# MotionDetectorProgJIG.net
KiCad netlist of a schematic drawn in Altium Designer
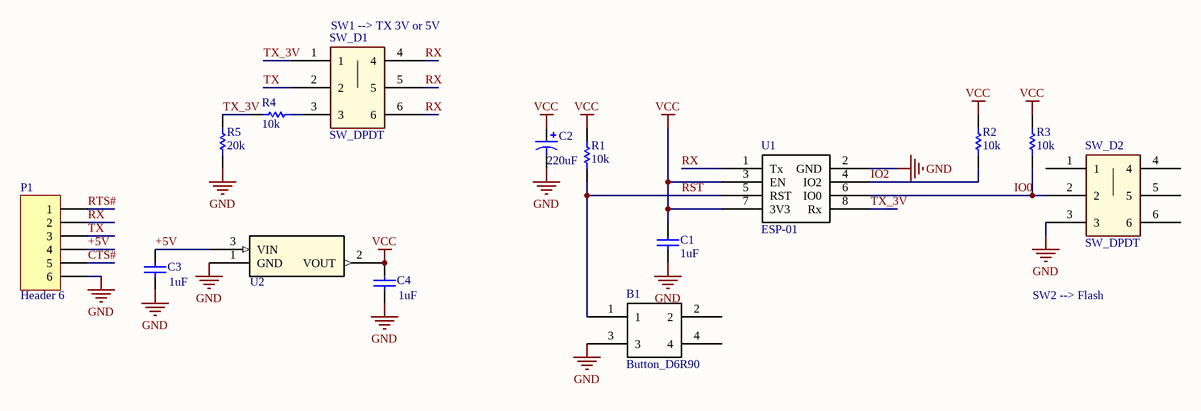
[diagram p0: MotionDetectorProgJIG.SchDoc]

(export (version "E")
  (design (tool "Eeschema 10.0.6"))
  (components
    (comp (ref "B1")
      (value "Button_D6R90")
      (footprint "Button_D6R90")
      (libsource (lib "MotionDetectorSchematicLib") (part "Button_D6R90"))
    )
    (comp (ref "C1")
      (value "1uF")
      (footprint "CAP_0804")
      (description "Capacitor")
      (fields (field (name "Comment") "Cap") (field (name "PUBLISHER") "Altium Limited"))
      (libsource (lib "Miscellaneous Devices") (part "Cap"))
    )
    (comp (ref "C2")
      (value "220uF")
      (footprint "U2-K")
      (description "Polarized Capacitor (Radial)")
      (fields (field (name "Comment") "Cap Pol1") (field (name "PUBLISHER") "Altium Limited"))
      (libsource (lib "Miscellaneous Devices") (part "Cap Pol1"))
    )
    (comp (ref "C3")
      (value "1uF")
      (footprint "CAP_0804")
      (description "Capacitor")
      (fields (field (name "Comment") "Cap") (field (name "PUBLISHER") "Altium Limited"))
      (libsource (lib "Miscellaneous Devices") (part "Cap"))
    )
    (comp (ref "C4")
      (value "1uF")
      (footprint "CAP_0804")
      (description "Capacitor")
      (fields (field (name "Comment") "Cap") (field (name "PUBLISHER") "Altium Limited"))
      (libsource (lib "Miscellaneous Devices") (part "Cap"))
    )
    (comp (ref "P1")
      (value "Header 6")
      (footprint "HDR1X6")
      (description "Header, 6-Pin")
      (fields (field (name "PUBLISHER") "Altium Limited"))
      (libsource (lib "Miscellaneous Connectors") (part "Header 6"))
    )
    (comp (ref "R1")
      (value "10k")
      (footprint "RES_0804_panasonic")
      (description "Resistor")
      (fields (field (name "Comment") "Res1") (field (name "PUBLISHER") "Altium Limited"))
      (libsource (lib "Miscellaneous Devices") (part "Res1"))
    )
    (comp (ref "R2")
      (value "10k")
      (footprint "RES_0804_panasonic")
      (description "Resistor")
      (fields (field (name "Comment") "Res1") (field (name "PUBLISHER") "Altium Limited"))
      (libsource (lib "Miscellaneous Devices") (part "Res1"))
    )
    (comp (ref "R3")
      (value "10k")
      (footprint "RES_0804_panasonic")
      (description "Resistor")
      (fields (field (name "Comment") "Res1") (field (name "PUBLISHER") "Altium Limited"))
      (libsource (lib "Miscellaneous Devices") (part "Res1"))
    )
    (comp (ref "R4")
      (value "10k")
      (footprint "RES_0804_panasonic")
      (description "Resistor")
      (fields (field (name "Comment") "Res1") (field (name "PUBLISHER") "Altium Limited"))
      (libsource (lib "Miscellaneous Devices") (part "Res1"))
    )
    (comp (ref "R5")
      (value "20k")
      (footprint "RES_0804_panasonic")
      (description "Resistor")
      (fields (field (name "Comment") "Res1") (field (name "PUBLISHER") "Altium Limited"))
      (libsource (lib "Miscellaneous Devices") (part "Res1"))
    )
    (comp (ref "SW_D1")
      (value "SW_DPDT")
      (footprint "SW_DPDT")
      (libsource (lib "MotionDetectorSchematicLib") (part "SW_DPDT"))
    )
    (comp (ref "SW_D2")
      (value "SW_DPDT")
      (footprint "SW_DPDT")
      (libsource (lib "MotionDetectorSchematicLib") (part "SW_DPDT"))
    )
    (comp (ref "U1")
      (value "ESP-01")
      (footprint "ESP-01")
      (libsource (lib "MotionDetectorSchematicLib") (part "ESP-01"))
    )
    (comp (ref "U2")
      (value "Voltage Reg")
      (footprint "SOT-23")
      (fields (field (name "MANUFACTURER_PART_NUMBER") "AP2120N-3.3TRG1"))
      (libsource (lib "MotionDetectorSchematicLib") (part "AP2120N-3.3TRG1"))
    )
  )
  (nets
    (net (code "1") (name "/+5V") (class "Default")
      (node (ref "C3") (pin "2") (pinfunction "2_2") (pintype "passive"))
      (node (ref "P1") (pin "4") (pinfunction "4_4") (pintype "passive"))
      (node (ref "U2") (pin "3") (pinfunction "VIN_3") (pintype "input"))
    )
    (net (code "2") (name "/CTS#") (class "Default")
      (node (ref "P1") (pin "5") (pinfunction "5_5") (pintype "passive"))
    )
    (net (code "3") (name "/IO0") (class "Default")
      (node (ref "R3") (pin "1") (pinfunction "1_1") (pintype "passive"))
      (node (ref "SW_D2") (pin "2") (pinfunction "2_2") (pintype "passive"))
      (node (ref "U1") (pin "6") (pinfunction "IO0_6") (pintype "passive"))
    )
    (net (code "4") (name "/IO2") (class "Default")
      (node (ref "R2") (pin "1") (pinfunction "1_1") (pintype "passive"))
      (node (ref "U1") (pin "4") (pinfunction "IO2_4") (pintype "passive"))
    )
    (net (code "5") (name "/RST") (class "Default")
      (node (ref "B1") (pin "1") (pinfunction "1_1") (pintype "passive"))
      (node (ref "R1") (pin "1") (pinfunction "1_1") (pintype "passive"))
      (node (ref "U1") (pin "5") (pinfunction "RST_5") (pintype "passive"))
    )
    (net (code "6") (name "/RTS#") (class "Default")
      (node (ref "P1") (pin "1") (pinfunction "1_1") (pintype "passive"))
    )
    (net (code "7") (name "/RX") (class "Default")
      (node (ref "P1") (pin "2") (pinfunction "2_2") (pintype "passive"))
      (node (ref "SW_D1") (pin "4") (pinfunction "4_4") (pintype "passive"))
      (node (ref "SW_D1") (pin "5") (pinfunction "5_5") (pintype "passive"))
      (node (ref "SW_D1") (pin "6") (pinfunction "6_6") (pintype "passive"))
      (node (ref "U1") (pin "1") (pinfunction "Tx_1") (pintype "passive"))
    )
    (net (code "8") (name "/TX") (class "Default")
      (node (ref "P1") (pin "3") (pinfunction "3_3") (pintype "passive"))
      (node (ref "SW_D1") (pin "2") (pinfunction "2_2") (pintype "passive"))
    )
    (net (code "9") (name "/TX_3V") (class "Default")
      (node (ref "R4") (pin "2") (pinfunction "2_2") (pintype "passive"))
      (node (ref "R5") (pin "1") (pinfunction "1_1") (pintype "passive"))
      (node (ref "SW_D1") (pin "1") (pinfunction "1_1") (pintype "passive"))
      (node (ref "U1") (pin "8") (pinfunction "Rx_8") (pintype "passive"))
    )
    (net (code "10") (name "GND") (class "Default")
      (node (ref "B1") (pin "3") (pinfunction "3_3") (pintype "passive"))
      (node (ref "C1") (pin "2") (pinfunction "2_2") (pintype "passive"))
      (node (ref "C2") (pin "2") (pinfunction "2_2") (pintype "passive"))
      (node (ref "C3") (pin "1") (pinfunction "1_1") (pintype "passive"))
      (node (ref "C4") (pin "1") (pinfunction "1_1") (pintype "passive"))
      (node (ref "P1") (pin "6") (pinfunction "6_6") (pintype "passive"))
      (node (ref "R5") (pin "2") (pinfunction "2_2") (pintype "passive"))
      (node (ref "SW_D2") (pin "3") (pinfunction "3_3") (pintype "passive"))
      (node (ref "U1") (pin "2") (pinfunction "GND_2") (pintype "passive"))
      (node (ref "U2") (pin "1") (pinfunction "GND_1") (pintype "power_in"))
    )
    (net (code "11") (name "Net-(R4-Pad1)") (class "Default")
      (node (ref "R4") (pin "1") (pinfunction "1_1") (pintype "passive"))
      (node (ref "SW_D1") (pin "3") (pinfunction "3_3") (pintype "passive"))
    )
    (net (code "12") (name "VCC") (class "Default")
      (node (ref "C1") (pin "1") (pinfunction "1_1") (pintype "passive"))
      (node (ref "C2") (pin "1") (pinfunction "1_1") (pintype "passive"))
      (node (ref "C4") (pin "2") (pinfunction "2_2") (pintype "passive"))
      (node (ref "R1") (pin "2") (pinfunction "2_2") (pintype "passive"))
      (node (ref "R2") (pin "2") (pinfunction "2_2") (pintype "passive"))
      (node (ref "R3") (pin "2") (pinfunction "2_2") (pintype "passive"))
      (node (ref "U1") (pin "3") (pinfunction "EN_3") (pintype "passive"))
      (node (ref "U1") (pin "7") (pinfunction "3V3_7") (pintype "passive"))
      (node (ref "U2") (pin "2") (pinfunction "VOUT_2") (pintype "output"))
    )
    (net (code "13") (name "unconnected-(B1-Pad2)") (class "Default")
      (node (ref "B1") (pin "2") (pinfunction "2_2") (pintype "passive"))
    )
    (net (code "14") (name "unconnected-(B1-Pad4)") (class "Default")
      (node (ref "B1") (pin "4") (pinfunction "4_4") (pintype "passive"))
    )
    (net (code "15") (name "unconnected-(SW_D2-Pad1)") (class "Default")
      (node (ref "SW_D2") (pin "1") (pinfunction "1_1") (pintype "passive"))
    )
    (net (code "16") (name "unconnected-(SW_D2-Pad4)") (class "Default")
      (node (ref "SW_D2") (pin "4") (pinfunction "4_4") (pintype "passive"))
    )
    (net (code "17") (name "unconnected-(SW_D2-Pad5)") (class "Default")
      (node (ref "SW_D2") (pin "5") (pinfunction "5_5") (pintype "passive"))
    )
    (net (code "18") (name "unconnected-(SW_D2-Pad6)") (class "Default")
      (node (ref "SW_D2") (pin "6") (pinfunction "6_6") (pintype "passive"))
    )
  )
)
